# Peripherals.net
KiCad netlist of a schematic drawn in Altium Designer
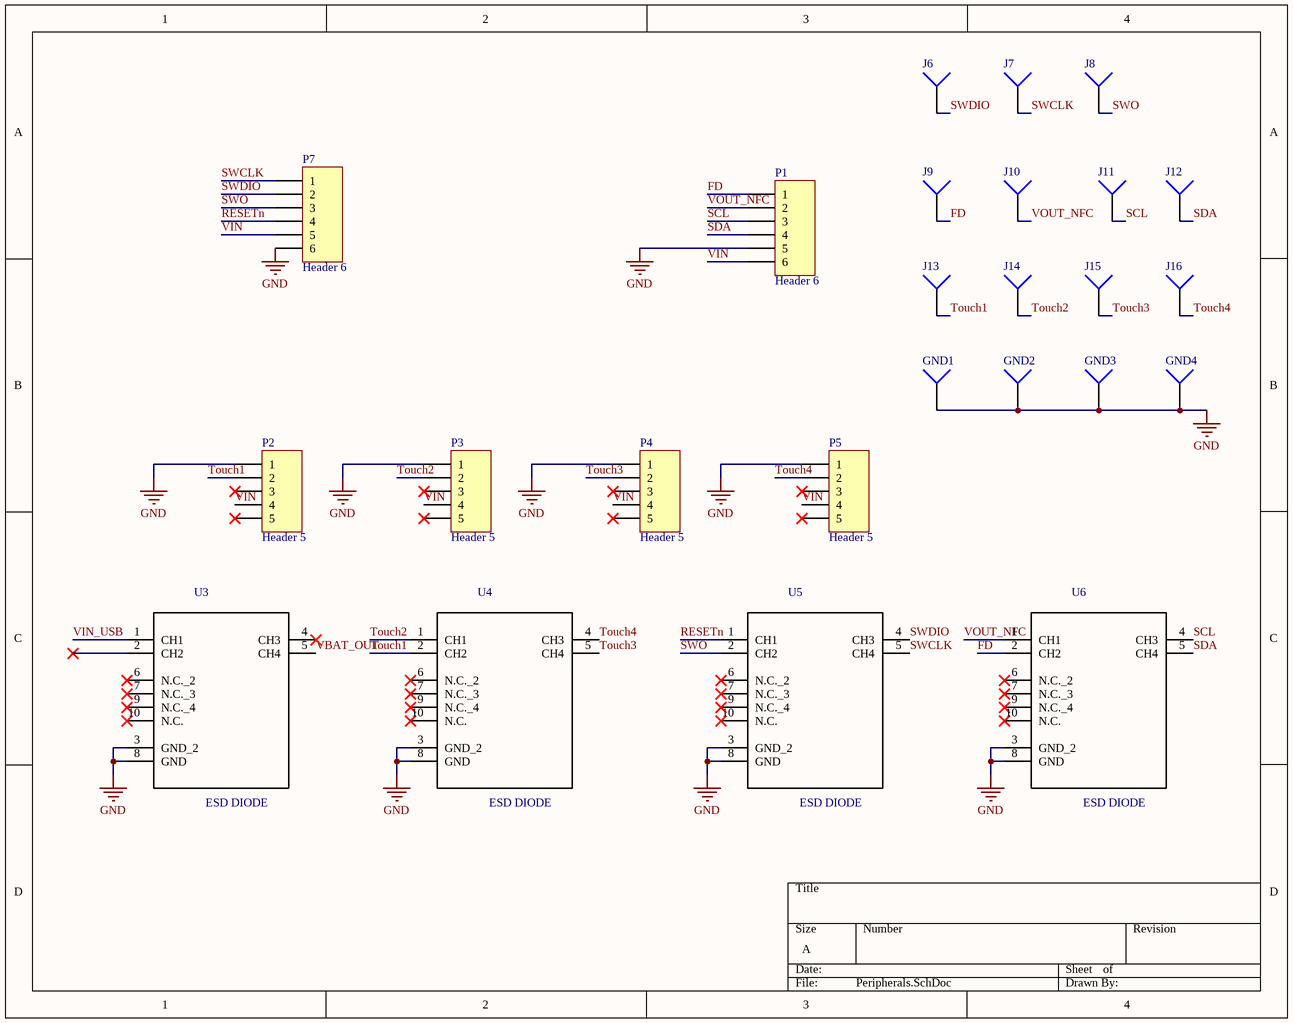
[diagram p0: Peripherals.SchDoc]

(export (version "E")
  (design (tool "Eeschema 10.0.6"))
  (components
    (comp (ref "GND1")
      (value "Socket")
      (footprint "PIN1")
      (fields (field (name "PUBLISHER") "Altium Limited"))
      (libsource (lib "Miscellaneous Connectors") (part "Socket"))
    )
    (comp (ref "GND2")
      (value "Socket")
      (footprint "PIN1")
      (fields (field (name "PUBLISHER") "Altium Limited"))
      (libsource (lib "Miscellaneous Connectors") (part "Socket"))
    )
    (comp (ref "GND3")
      (value "Socket")
      (footprint "PIN1")
      (fields (field (name "PUBLISHER") "Altium Limited"))
      (libsource (lib "Miscellaneous Connectors") (part "Socket"))
    )
    (comp (ref "GND4")
      (value "Socket")
      (footprint "PIN1")
      (fields (field (name "PUBLISHER") "Altium Limited"))
      (libsource (lib "Miscellaneous Connectors") (part "Socket"))
    )
    (comp (ref "J6")
      (value "Socket")
      (footprint "PIN1")
      (fields (field (name "PUBLISHER") "Altium Limited"))
      (libsource (lib "Miscellaneous Connectors") (part "Socket"))
    )
    (comp (ref "J7")
      (value "Socket")
      (footprint "PIN1")
      (fields (field (name "PUBLISHER") "Altium Limited"))
      (libsource (lib "Miscellaneous Connectors") (part "Socket"))
    )
    (comp (ref "J8")
      (value "Socket")
      (footprint "PIN1")
      (fields (field (name "PUBLISHER") "Altium Limited"))
      (libsource (lib "Miscellaneous Connectors") (part "Socket"))
    )
    (comp (ref "J9")
      (value "Socket")
      (footprint "PIN1")
      (fields (field (name "PUBLISHER") "Altium Limited"))
      (libsource (lib "Miscellaneous Connectors") (part "Socket"))
    )
    (comp (ref "J10")
      (value "Socket")
      (footprint "PIN1")
      (fields (field (name "PUBLISHER") "Altium Limited"))
      (libsource (lib "Miscellaneous Connectors") (part "Socket"))
    )
    (comp (ref "J11")
      (value "Socket")
      (footprint "PIN1")
      (fields (field (name "PUBLISHER") "Altium Limited"))
      (libsource (lib "Miscellaneous Connectors") (part "Socket"))
    )
    (comp (ref "J12")
      (value "Socket")
      (footprint "PIN1")
      (fields (field (name "PUBLISHER") "Altium Limited"))
      (libsource (lib "Miscellaneous Connectors") (part "Socket"))
    )
    (comp (ref "J13")
      (value "Socket")
      (footprint "PIN1")
      (fields (field (name "PUBLISHER") "Altium Limited"))
      (libsource (lib "Miscellaneous Connectors") (part "Socket"))
    )
    (comp (ref "J14")
      (value "Socket")
      (footprint "PIN1")
      (fields (field (name "PUBLISHER") "Altium Limited"))
      (libsource (lib "Miscellaneous Connectors") (part "Socket"))
    )
    (comp (ref "J15")
      (value "Socket")
      (footprint "PIN1")
      (fields (field (name "PUBLISHER") "Altium Limited"))
      (libsource (lib "Miscellaneous Connectors") (part "Socket"))
    )
    (comp (ref "J16")
      (value "Socket")
      (footprint "PIN1")
      (fields (field (name "PUBLISHER") "Altium Limited"))
      (libsource (lib "Miscellaneous Connectors") (part "Socket"))
    )
    (comp (ref "P1")
      (value "Header 6")
      (footprint "HDR1X6")
      (description "Header, 6-Pin")
      (fields (field (name "PUBLISHER") "Altium Limited"))
      (libsource (lib "Miscellaneous Connectors") (part "Header 6"))
    )
    (comp (ref "P2")
      (value "Header 5")
      (footprint "HDR1X5")
      (description "Header, 5-Pin")
      (fields (field (name "PUBLISHER") "Altium Limited"))
      (libsource (lib "Miscellaneous Connectors") (part "Header 5"))
    )
    (comp (ref "P3")
      (value "Header 5")
      (footprint "HDR1X5")
      (description "Header, 5-Pin")
      (fields (field (name "PUBLISHER") "Altium Limited"))
      (libsource (lib "Miscellaneous Connectors") (part "Header 5"))
    )
    (comp (ref "P4")
      (value "Header 5")
      (footprint "HDR1X5")
      (description "Header, 5-Pin")
      (fields (field (name "PUBLISHER") "Altium Limited"))
      (libsource (lib "Miscellaneous Connectors") (part "Header 5"))
    )
    (comp (ref "P5")
      (value "Header 5")
      (footprint "HDR1X5")
      (description "Header, 5-Pin")
      (fields (field (name "PUBLISHER") "Altium Limited"))
      (libsource (lib "Miscellaneous Connectors") (part "Header 5"))
    )
    (comp (ref "P7")
      (value "Header 6")
      (footprint "HDR1X6")
      (description "Header, 6-Pin")
      (fields (field (name "PUBLISHER") "Altium Limited"))
      (libsource (lib "Miscellaneous Connectors") (part "Header 6"))
    )
    (comp (ref "U3")
      (value "ESD DIODE")
      (footprint "SON50P100X255X50-10N")
      (description "TVS DIODE DFN2510A-10")
      (fields
        (field (name "DIGI-KEY PART NUMBER") "1727-7821-1-ND")
        (field (name "MANUFACTURER") "Nexperia USA Inc.")
      )
      (libsource (lib "phone_cover_parts") (part "IP4292CZ10-TBR"))
    )
    (comp (ref "U4")
      (value "ESD DIODE")
      (footprint "SON50P100X255X50-10N")
      (description "TVS DIODE DFN2510A-10")
      (fields
        (field (name "DIGI-KEY PART NUMBER") "1727-7821-1-ND")
        (field (name "MANUFACTURER") "Nexperia USA Inc.")
      )
      (libsource (lib "phone_cover_parts") (part "IP4292CZ10-TBR"))
    )
    (comp (ref "U5")
      (value "ESD DIODE")
      (footprint "SON50P100X255X50-10N")
      (description "TVS DIODE DFN2510A-10")
      (fields
        (field (name "DIGI-KEY PART NUMBER") "1727-7821-1-ND")
        (field (name "MANUFACTURER") "Nexperia USA Inc.")
      )
      (libsource (lib "phone_cover_parts") (part "IP4292CZ10-TBR"))
    )
    (comp (ref "U6")
      (value "ESD DIODE")
      (footprint "SON50P100X255X50-10N")
      (description "TVS DIODE DFN2510A-10")
      (fields
        (field (name "DIGI-KEY PART NUMBER") "1727-7821-1-ND")
        (field (name "MANUFACTURER") "Nexperia USA Inc.")
      )
      (libsource (lib "phone_cover_parts") (part "IP4292CZ10-TBR"))
    )
  )
  (nets
    (net (code "1") (name "/FD") (class "Default")
      (node (ref "J9") (pin "1") (pinfunction "1_1") (pintype "passive"))
      (node (ref "P1") (pin "1") (pinfunction "1_1") (pintype "passive"))
      (node (ref "U6") (pin "2") (pinfunction "CH2_2") (pintype "passive"))
    )
    (net (code "2") (name "/RESETn") (class "Default")
      (node (ref "P7") (pin "4") (pinfunction "4_4") (pintype "passive"))
      (node (ref "U5") (pin "1") (pinfunction "CH1_1") (pintype "passive"))
    )
    (net (code "3") (name "/SCL") (class "Default")
      (node (ref "J11") (pin "1") (pinfunction "1_1") (pintype "passive"))
      (node (ref "P1") (pin "3") (pinfunction "3_3") (pintype "passive"))
      (node (ref "U6") (pin "4") (pinfunction "CH3_4") (pintype "passive"))
    )
    (net (code "4") (name "/SDA") (class "Default")
      (node (ref "J12") (pin "1") (pinfunction "1_1") (pintype "passive"))
      (node (ref "P1") (pin "4") (pinfunction "4_4") (pintype "passive"))
      (node (ref "U6") (pin "5") (pinfunction "CH4_5") (pintype "passive"))
    )
    (net (code "5") (name "/SWCLK") (class "Default")
      (node (ref "J7") (pin "1") (pinfunction "1_1") (pintype "passive"))
      (node (ref "P7") (pin "1") (pinfunction "1_1") (pintype "passive"))
      (node (ref "U5") (pin "5") (pinfunction "CH4_5") (pintype "passive"))
    )
    (net (code "6") (name "/SWDIO") (class "Default")
      (node (ref "J6") (pin "1") (pinfunction "1_1") (pintype "passive"))
      (node (ref "P7") (pin "2") (pinfunction "2_2") (pintype "passive"))
      (node (ref "U5") (pin "4") (pinfunction "CH3_4") (pintype "passive"))
    )
    (net (code "7") (name "/SWO") (class "Default")
      (node (ref "J8") (pin "1") (pinfunction "1_1") (pintype "passive"))
      (node (ref "P7") (pin "3") (pinfunction "3_3") (pintype "passive"))
      (node (ref "U5") (pin "2") (pinfunction "CH2_2") (pintype "passive"))
    )
    (net (code "8") (name "/Touch1") (class "Default")
      (node (ref "J13") (pin "1") (pinfunction "1_1") (pintype "passive"))
      (node (ref "P2") (pin "2") (pinfunction "2_2") (pintype "passive"))
      (node (ref "U4") (pin "2") (pinfunction "CH2_2") (pintype "passive"))
    )
    (net (code "9") (name "/Touch2") (class "Default")
      (node (ref "J14") (pin "1") (pinfunction "1_1") (pintype "passive"))
      (node (ref "P3") (pin "2") (pinfunction "2_2") (pintype "passive"))
      (node (ref "U4") (pin "1") (pinfunction "CH1_1") (pintype "passive"))
    )
    (net (code "10") (name "/Touch3") (class "Default")
      (node (ref "J15") (pin "1") (pinfunction "1_1") (pintype "passive"))
      (node (ref "P4") (pin "2") (pinfunction "2_2") (pintype "passive"))
      (node (ref "U4") (pin "5") (pinfunction "CH4_5") (pintype "passive"))
    )
    (net (code "11") (name "/Touch4") (class "Default")
      (node (ref "J16") (pin "1") (pinfunction "1_1") (pintype "passive"))
      (node (ref "P5") (pin "2") (pinfunction "2_2") (pintype "passive"))
      (node (ref "U4") (pin "4") (pinfunction "CH3_4") (pintype "passive"))
    )
    (net (code "12") (name "/VBAT_OUT") (class "Default")
      (node (ref "U3") (pin "5") (pinfunction "CH4_5") (pintype "passive"))
    )
    (net (code "13") (name "/VIN") (class "Default")
      (node (ref "P1") (pin "6") (pinfunction "6_6") (pintype "passive"))
      (node (ref "P2") (pin "4") (pinfunction "4_4") (pintype "passive"))
      (node (ref "P3") (pin "4") (pinfunction "4_4") (pintype "passive"))
      (node (ref "P4") (pin "4") (pinfunction "4_4") (pintype "passive"))
      (node (ref "P5") (pin "4") (pinfunction "4_4") (pintype "passive"))
      (node (ref "P7") (pin "5") (pinfunction "5_5") (pintype "passive"))
    )
    (net (code "14") (name "/VIN_USB") (class "Default")
      (node (ref "U3") (pin "1") (pinfunction "CH1_1") (pintype "passive"))
    )
    (net (code "15") (name "/VOUT_NFC") (class "Default")
      (node (ref "J10") (pin "1") (pinfunction "1_1") (pintype "passive"))
      (node (ref "P1") (pin "2") (pinfunction "2_2") (pintype "passive"))
      (node (ref "U6") (pin "1") (pinfunction "CH1_1") (pintype "passive"))
    )
    (net (code "16") (name "GND") (class "Default")
      (node (ref "GND1") (pin "1") (pinfunction "1_1") (pintype "passive"))
      (node (ref "GND2") (pin "1") (pinfunction "1_1") (pintype "passive"))
      (node (ref "GND3") (pin "1") (pinfunction "1_1") (pintype "passive"))
      (node (ref "GND4") (pin "1") (pinfunction "1_1") (pintype "passive"))
      (node (ref "P1") (pin "5") (pinfunction "5_5") (pintype "passive"))
      (node (ref "P2") (pin "1") (pinfunction "1_1") (pintype "passive"))
      (node (ref "P3") (pin "1") (pinfunction "1_1") (pintype "passive"))
      (node (ref "P4") (pin "1") (pinfunction "1_1") (pintype "passive"))
      (node (ref "P5") (pin "1") (pinfunction "1_1") (pintype "passive"))
      (node (ref "P7") (pin "6") (pinfunction "6_6") (pintype "passive"))
      (node (ref "U3") (pin "3") (pinfunction "GND_2_3") (pintype "passive"))
      (node (ref "U3") (pin "8") (pinfunction "GND_8") (pintype "passive"))
      (node (ref "U4") (pin "3") (pinfunction "GND_2_3") (pintype "passive"))
      (node (ref "U4") (pin "8") (pinfunction "GND_8") (pintype "passive"))
      (node (ref "U5") (pin "3") (pinfunction "GND_2_3") (pintype "passive"))
      (node (ref "U5") (pin "8") (pinfunction "GND_8") (pintype "passive"))
      (node (ref "U6") (pin "3") (pinfunction "GND_2_3") (pintype "passive"))
      (node (ref "U6") (pin "8") (pinfunction "GND_8") (pintype "passive"))
    )
    (net (code "17") (name "unconnected-(P2-Pad3)") (class "Default")
      (node (ref "P2") (pin "3") (pinfunction "3_3") (pintype "passive+no_connect"))
    )
    (net (code "18") (name "unconnected-(P2-Pad5)") (class "Default")
      (node (ref "P2") (pin "5") (pinfunction "5_5") (pintype "passive+no_connect"))
    )
    (net (code "19") (name "unconnected-(P3-Pad3)") (class "Default")
      (node (ref "P3") (pin "3") (pinfunction "3_3") (pintype "passive+no_connect"))
    )
    (net (code "20") (name "unconnected-(P3-Pad5)") (class "Default")
      (node (ref "P3") (pin "5") (pinfunction "5_5") (pintype "passive+no_connect"))
    )
    (net (code "21") (name "unconnected-(P4-Pad3)") (class "Default")
      (node (ref "P4") (pin "3") (pinfunction "3_3") (pintype "passive+no_connect"))
    )
    (net (code "22") (name "unconnected-(P4-Pad5)") (class "Default")
      (node (ref "P4") (pin "5") (pinfunction "5_5") (pintype "passive+no_connect"))
    )
    (net (code "23") (name "unconnected-(P5-Pad3)") (class "Default")
      (node (ref "P5") (pin "3") (pinfunction "3_3") (pintype "passive+no_connect"))
    )
    (net (code "24") (name "unconnected-(P5-Pad5)") (class "Default")
      (node (ref "P5") (pin "5") (pinfunction "5_5") (pintype "passive+no_connect"))
    )
    (net (code "25") (name "unconnected-(U3-CH2-Pad2)") (class "Default")
      (node (ref "U3") (pin "2") (pinfunction "CH2_2") (pintype "passive+no_connect"))
    )
    (net (code "26") (name "unconnected-(U3-CH3-Pad4)") (class "Default")
      (node (ref "U3") (pin "4") (pinfunction "CH3_4") (pintype "passive+no_connect"))
    )
    (net (code "27") (name "unconnected-(U3-N.C.-Pad10)") (class "Default")
      (node (ref "U3") (pin "10") (pinfunction "N.C._10") (pintype "passive+no_connect"))
    )
    (net (code "28") (name "unconnected-(U3-N.C._2-Pad6)") (class "Default")
      (node (ref "U3") (pin "6") (pinfunction "N.C._2_6") (pintype "passive+no_connect"))
    )
    (net (code "29") (name "unconnected-(U3-N.C._3-Pad7)") (class "Default")
      (node (ref "U3") (pin "7") (pinfunction "N.C._3_7") (pintype "passive+no_connect"))
    )
    (net (code "30") (name "unconnected-(U3-N.C._4-Pad9)") (class "Default")
      (node (ref "U3") (pin "9") (pinfunction "N.C._4_9") (pintype "passive+no_connect"))
    )
    (net (code "31") (name "unconnected-(U4-N.C.-Pad10)") (class "Default")
      (node (ref "U4") (pin "10") (pinfunction "N.C._10") (pintype "passive+no_connect"))
    )
    (net (code "32") (name "unconnected-(U4-N.C._2-Pad6)") (class "Default")
      (node (ref "U4") (pin "6") (pinfunction "N.C._2_6") (pintype "passive+no_connect"))
    )
    (net (code "33") (name "unconnected-(U4-N.C._3-Pad7)") (class "Default")
      (node (ref "U4") (pin "7") (pinfunction "N.C._3_7") (pintype "passive+no_connect"))
    )
    (net (code "34") (name "unconnected-(U4-N.C._4-Pad9)") (class "Default")
      (node (ref "U4") (pin "9") (pinfunction "N.C._4_9") (pintype "passive+no_connect"))
    )
    (net (code "35") (name "unconnected-(U5-N.C.-Pad10)") (class "Default")
      (node (ref "U5") (pin "10") (pinfunction "N.C._10") (pintype "passive+no_connect"))
    )
    (net (code "36") (name "unconnected-(U5-N.C._2-Pad6)") (class "Default")
      (node (ref "U5") (pin "6") (pinfunction "N.C._2_6") (pintype "passive+no_connect"))
    )
    (net (code "37") (name "unconnected-(U5-N.C._3-Pad7)") (class "Default")
      (node (ref "U5") (pin "7") (pinfunction "N.C._3_7") (pintype "passive+no_connect"))
    )
    (net (code "38") (name "unconnected-(U5-N.C._4-Pad9)") (class "Default")
      (node (ref "U5") (pin "9") (pinfunction "N.C._4_9") (pintype "passive+no_connect"))
    )
    (net (code "39") (name "unconnected-(U6-N.C.-Pad10)") (class "Default")
      (node (ref "U6") (pin "10") (pinfunction "N.C._10") (pintype "passive+no_connect"))
    )
    (net (code "40") (name "unconnected-(U6-N.C._2-Pad6)") (class "Default")
      (node (ref "U6") (pin "6") (pinfunction "N.C._2_6") (pintype "passive+no_connect"))
    )
    (net (code "41") (name "unconnected-(U6-N.C._3-Pad7)") (class "Default")
      (node (ref "U6") (pin "7") (pinfunction "N.C._3_7") (pintype "passive+no_connect"))
    )
    (net (code "42") (name "unconnected-(U6-N.C._4-Pad9)") (class "Default")
      (node (ref "U6") (pin "9") (pinfunction "N.C._4_9") (pintype "passive+no_connect"))
    )
  )
)
